# POWER.net
KiCad netlist of a schematic drawn in Altium Designer
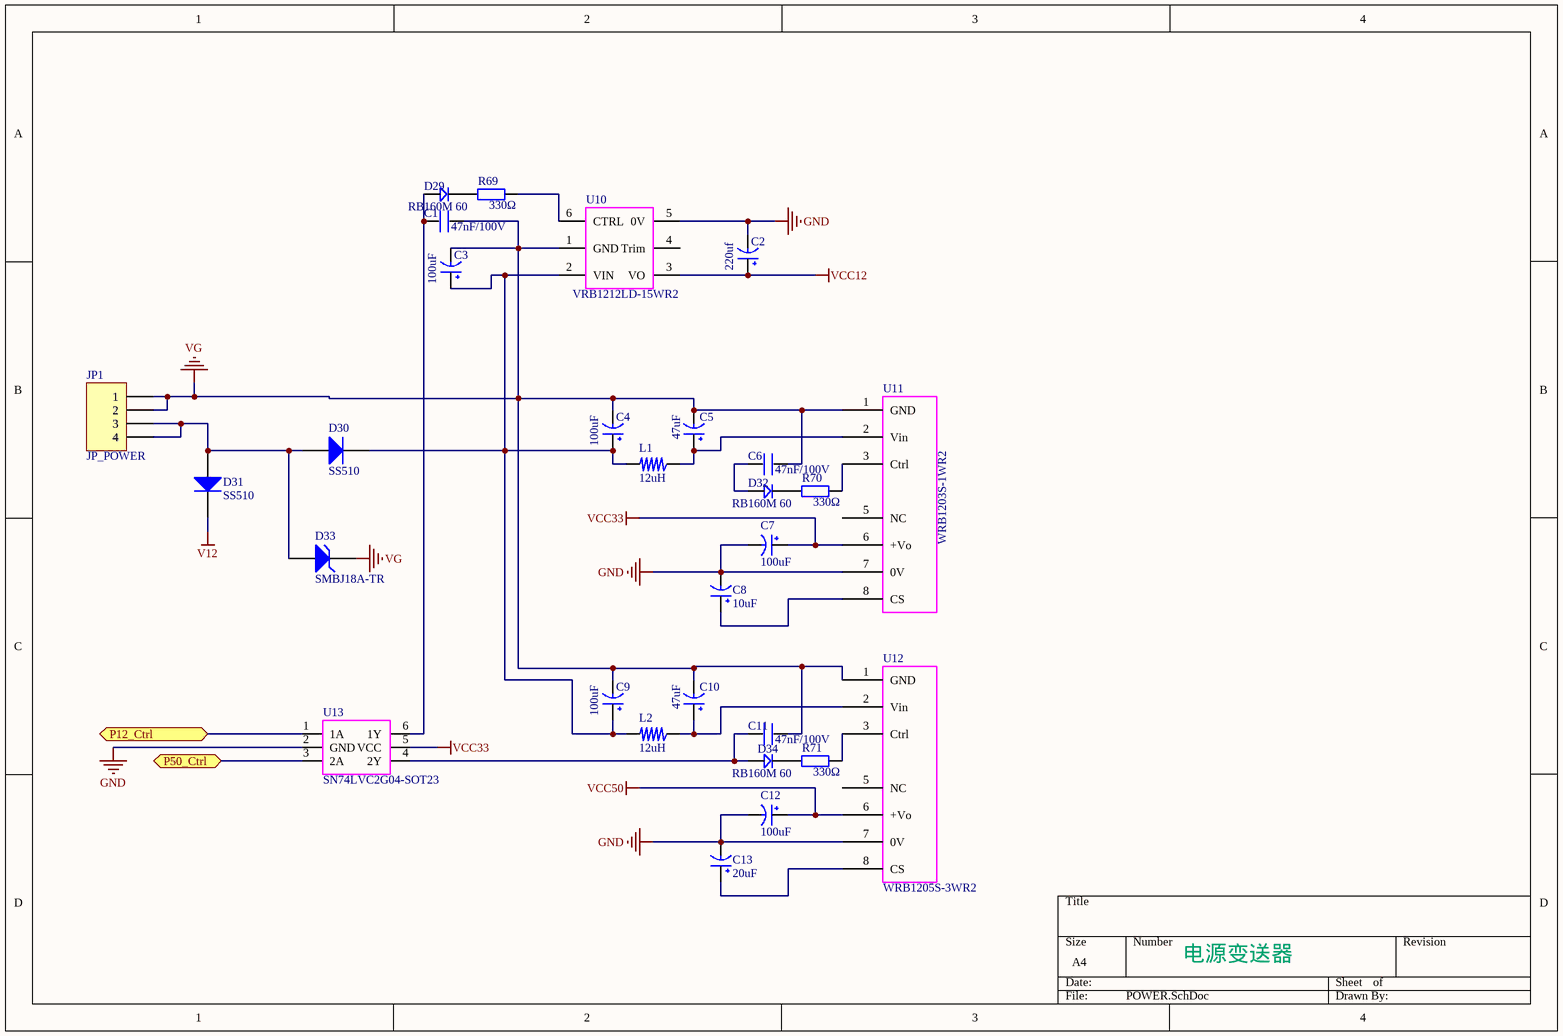
[diagram p0: POWER.SchDoc]

(export (version "E")
  (design (tool "Eeschema 10.0.6"))
  (components
    (comp (ref "C1") (value "47nF/100V") (footprint "0603P") (libsource (lib "WARSHIP") (part "C")))
    (comp (ref "C2") (value "220uf") (footprint "SMD-EC-F6.3") (libsource (lib "") (part "CAP_1")))
    (comp (ref "C3") (value "100uF") (footprint "SMD-EC-F6.3") (libsource (lib "") (part "CAP_1")))
    (comp (ref "C4") (value "100uF") (footprint "SMD-EC-F6.3") (libsource (lib "") (part "CAP_1")))
    (comp (ref "C5") (value "47uF") (footprint "SMD-EC-F6.3") (libsource (lib "") (part "CAP_1")))
    (comp (ref "C6") (value "47nF/100V") (footprint "0603P") (libsource (lib "WARSHIP") (part "C")))
    (comp (ref "C7") (value "100uF") (footprint "SMD-EC-F6.3") (libsource (lib "WARSHIP") (part "CAP")))
    (comp (ref "C8") (value "10uF") (footprint "SMD-EC-F4") (libsource (lib "") (part "CAP_1")))
    (comp (ref "C9") (value "100uF") (footprint "SMD-EC-F6.3") (libsource (lib "") (part "CAP_1")))
    (comp (ref "C10") (value "47uF") (footprint "SMD-EC-F6.3") (libsource (lib "") (part "CAP_1")))
    (comp (ref "C11") (value "47nF/100V") (footprint "0603P") (libsource (lib "WARSHIP") (part "C")))
    (comp (ref "C12") (value "100uF") (footprint "SMD-EC-F6.3") (libsource (lib "WARSHIP") (part "CAP")))
    (comp (ref "C13") (value "20uF") (footprint "SMD-EC-F4") (libsource (lib "") (part "CAP_1")))
    (comp (ref "D29") (value "RB160M 60") (footprint "SOD123/X.85") (libsource (lib "WARSHIP") (part "D")))
    (comp (ref "D30")
      (value "SS510")
      (footprint "SMC")
      (description "Default Diode")
      (fields (field (name "PUBLISHER") "Altium Limited"))
      (libsource (lib "Miscellaneous Devices") (part "Diode"))
    )
    (comp (ref "D31")
      (value "SS510")
      (footprint "SMC")
      (description "Default Diode")
      (fields (field (name "PUBLISHER") "Altium Limited"))
      (libsource (lib "Miscellaneous Devices") (part "Diode"))
    )
    (comp (ref "D32") (value "RB160M 60") (footprint "SOD123/X.85") (libsource (lib "WARSHIP") (part "D")))
    (comp (ref "D33")
      (value "SMBJ18A-TR")
      (footprint "DO-214")
      (description "Zener Diode")
      (fields (field (name "PUBLISHER") "Altium Limited"))
      (libsource (lib "Miscellaneous Devices") (part "D Zener"))
    )
    (comp (ref "D34") (value "RB160M 60") (footprint "SOD123/X.85") (libsource (lib "WARSHIP") (part "D")))
    (comp (ref "JP1")
      (value "JP_POWER")
      (footprint "3.81-4P")
      (description "Header, 4-Pin")
      (fields (field (name "PUBLISHER") "Altium Limited"))
      (libsource (lib "Miscellaneous Connectors") (part "Header 4"))
    )
    (comp (ref "L1") (value "12uH") (footprint "4R7_L_7_7_4") (libsource (lib "WARSHIP") (part "L_SOP")))
    (comp (ref "L2") (value "12uH") (footprint "4R7_L_7_7_4") (libsource (lib "WARSHIP") (part "L_SOP")))
    (comp (ref "R69")
      (value "330Ω")
      (footprint "1206")
      (description "Resistor")
      (fields (field (name "Comment") "Res2") (field (name "PUBLISHER") "Altium Limited"))
      (libsource (lib "Miscellaneous Devices") (part "Res2"))
    )
    (comp (ref "R70")
      (value "330Ω")
      (footprint "1206")
      (description "Resistor")
      (fields (field (name "Comment") "Res2") (field (name "PUBLISHER") "Altium Limited"))
      (libsource (lib "Miscellaneous Devices") (part "Res2"))
    )
    (comp (ref "R71")
      (value "330Ω")
      (footprint "1206")
      (description "Resistor")
      (fields (field (name "Comment") "Res2") (field (name "PUBLISHER") "Altium Limited"))
      (libsource (lib "Miscellaneous Devices") (part "Res2"))
    )
    (comp (ref "U10")
      (value "VRB1212LD-15WR2")
      (footprint "VRB1212LD-15WR2")
      (libsource (lib "VRB1212LD-15WR2") (part "VRB1212LD-15WR2"))
    )
    (comp (ref "U11")
      (value "WRB1203S-1WR2")
      (footprint "WRB120XS-XWR2")
      (libsource (lib "WRB1203S-1WR2") (part "WRB1203S-1WR2"))
    )
    (comp (ref "U12")
      (value "WRB1205S-3WR2")
      (footprint "WRB120XS-XWR2")
      (libsource (lib "WRB1203S-1WR2") (part "WRB1205S-3WR2"))
    )
    (comp (ref "U13")
      (value "SN74LVC2G04-SOT23")
      (footprint "SOT23-6")
      (libsource (lib "74hc245") (part "SN74LVC2G04-SOT23"))
    )
  )
  (nets
    (net (code "1") (name "/P12_Ctrl") (class "Default")
      (node (ref "U13") (pin "1") (pinfunction "1A_1") (pintype "passive"))
    )
    (net (code "2") (name "/P50_Ctrl") (class "Default")
      (node (ref "U13") (pin "3") (pinfunction "2A_3") (pintype "passive"))
    )
    (net (code "3") (name "GND") (class "Default")
      (node (ref "C12") (pin "2") (pinfunction "GND_2") (pintype "passive"))
      (node (ref "C13") (pin "2") (pinfunction "GND_2") (pintype "passive"))
      (node (ref "C2") (pin "2") (pinfunction "GND_2") (pintype "passive"))
      (node (ref "C7") (pin "2") (pinfunction "GND_2") (pintype "passive"))
      (node (ref "C8") (pin "2") (pinfunction "GND_2") (pintype "passive"))
      (node (ref "U10") (pin "5") (pinfunction "0V_5") (pintype "passive"))
      (node (ref "U11") (pin "7") (pinfunction "0V_7") (pintype "passive"))
      (node (ref "U12") (pin "7") (pinfunction "0V_7") (pintype "passive"))
      (node (ref "U13") (pin "2") (pinfunction "GND_2") (pintype "passive"))
    )
    (net (code "4") (name "Net-(C3-VCC)") (class "Default")
      (node (ref "C3") (pin "1") (pinfunction "VCC_1") (pintype "passive"))
      (node (ref "C4") (pin "1") (pinfunction "VCC_1") (pintype "passive"))
      (node (ref "C9") (pin "1") (pinfunction "VCC_1") (pintype "passive"))
      (node (ref "D30") (pin "2") (pinfunction "K_2") (pintype "passive"))
      (node (ref "L1") (pin "2") (pinfunction "2_2") (pintype "passive"))
      (node (ref "L2") (pin "2") (pinfunction "2_2") (pintype "passive"))
      (node (ref "U10") (pin "2") (pinfunction "VIN_2") (pintype "passive"))
    )
    (net (code "5") (name "Net-(C5-VCC)") (class "Default")
      (node (ref "C5") (pin "1") (pinfunction "VCC_1") (pintype "passive"))
      (node (ref "L1") (pin "1") (pinfunction "1_1") (pintype "passive"))
      (node (ref "U11") (pin "2") (pinfunction "Vin_2") (pintype "passive"))
    )
    (net (code "6") (name "Net-(C6-Pad1)") (class "Default")
      (node (ref "C6") (pin "1") (pintype "passive"))
      (node (ref "D32") (pin "1") (pintype "passive"))
    )
    (net (code "7") (name "Net-(C8-VCC)") (class "Default")
      (node (ref "C8") (pin "1") (pinfunction "VCC_1") (pintype "passive"))
      (node (ref "U11") (pin "8") (pinfunction "CS_8") (pintype "passive"))
    )
    (net (code "8") (name "Net-(C10-VCC)") (class "Default")
      (node (ref "C10") (pin "1") (pinfunction "VCC_1") (pintype "passive"))
      (node (ref "L2") (pin "1") (pinfunction "1_1") (pintype "passive"))
      (node (ref "U12") (pin "2") (pinfunction "Vin_2") (pintype "passive"))
    )
    (net (code "9") (name "Net-(C13-VCC)") (class "Default")
      (node (ref "C13") (pin "1") (pinfunction "VCC_1") (pintype "passive"))
      (node (ref "U12") (pin "8") (pinfunction "CS_8") (pintype "passive"))
    )
    (net (code "10") (name "Net-(D29-Pad2)") (class "Default")
      (node (ref "D29") (pin "2") (pintype "passive"))
      (node (ref "R69") (pin "2") (pinfunction "2_2") (pintype "passive"))
    )
    (net (code "11") (name "Net-(D30-A)") (class "Default")
      (node (ref "D30") (pin "1") (pinfunction "A_1") (pintype "passive"))
      (node (ref "D31") (pin "1") (pinfunction "A_1") (pintype "passive"))
      (node (ref "D33") (pin "1") (pinfunction "A_1") (pintype "passive"))
      (node (ref "JP1") (pin "3") (pinfunction "3_3") (pintype "passive"))
      (node (ref "JP1") (pin "4") (pinfunction "4_4") (pintype "passive"))
    )
    (net (code "12") (name "Net-(D32-Pad2)") (class "Default")
      (node (ref "D32") (pin "2") (pintype "passive"))
      (node (ref "R70") (pin "2") (pinfunction "2_2") (pintype "passive"))
    )
    (net (code "13") (name "Net-(D34-Pad2)") (class "Default")
      (node (ref "D34") (pin "2") (pintype "passive"))
      (node (ref "R71") (pin "2") (pinfunction "2_2") (pintype "passive"))
    )
    (net (code "14") (name "Net-(U10-CTRL)") (class "Default")
      (node (ref "R69") (pin "1") (pinfunction "1_1") (pintype "passive"))
      (node (ref "U10") (pin "6") (pinfunction "CTRL_6") (pintype "passive"))
    )
    (net (code "15") (name "Net-(U11-Ctrl)") (class "Default")
      (node (ref "R70") (pin "1") (pinfunction "1_1") (pintype "passive"))
      (node (ref "U11") (pin "3") (pinfunction "Ctrl_3") (pintype "passive"))
    )
    (net (code "16") (name "Net-(U12-Ctrl)") (class "Default")
      (node (ref "R71") (pin "1") (pinfunction "1_1") (pintype "passive"))
      (node (ref "U12") (pin "3") (pinfunction "Ctrl_3") (pintype "passive"))
    )
    (net (code "17") (name "Net-(U13-1Y)") (class "Default")
      (node (ref "C1") (pin "1") (pintype "passive"))
      (node (ref "D29") (pin "1") (pintype "passive"))
      (node (ref "U13") (pin "6") (pinfunction "1Y_6") (pintype "passive"))
    )
    (net (code "18") (name "Net-(U13-2Y)") (class "Default")
      (node (ref "C11") (pin "1") (pintype "passive"))
      (node (ref "D34") (pin "1") (pintype "passive"))
      (node (ref "U13") (pin "4") (pinfunction "2Y_4") (pintype "passive"))
    )
    (net (code "19") (name "V12") (class "Default")
      (node (ref "D31") (pin "2") (pinfunction "K_2") (pintype "passive"))
    )
    (net (code "20") (name "VCC12") (class "Default")
      (node (ref "C2") (pin "1") (pinfunction "VCC_1") (pintype "passive"))
      (node (ref "U10") (pin "3") (pinfunction "VO_3") (pintype "passive"))
    )
    (net (code "21") (name "VCC33") (class "Default")
      (node (ref "C7") (pin "1") (pinfunction "VCC_1") (pintype "passive"))
      (node (ref "U11") (pin "6") (pinfunction "+Vo_6") (pintype "passive"))
      (node (ref "U13") (pin "5") (pinfunction "VCC_5") (pintype "passive"))
    )
    (net (code "22") (name "VCC50") (class "Default")
      (node (ref "C12") (pin "1") (pinfunction "VCC_1") (pintype "passive"))
      (node (ref "U12") (pin "6") (pinfunction "+Vo_6") (pintype "passive"))
    )
    (net (code "23") (name "VG") (class "Default")
      (node (ref "C1") (pin "2") (pintype "passive"))
      (node (ref "C10") (pin "2") (pinfunction "GND_2") (pintype "passive"))
      (node (ref "C11") (pin "2") (pintype "passive"))
      (node (ref "C3") (pin "2") (pinfunction "GND_2") (pintype "passive"))
      (node (ref "C4") (pin "2") (pinfunction "GND_2") (pintype "passive"))
      (node (ref "C5") (pin "2") (pinfunction "GND_2") (pintype "passive"))
      (node (ref "C6") (pin "2") (pintype "passive"))
      (node (ref "C9") (pin "2") (pinfunction "GND_2") (pintype "passive"))
      (node (ref "D33") (pin "2") (pinfunction "K_2") (pintype "passive"))
      (node (ref "JP1") (pin "1") (pinfunction "1_1") (pintype "passive"))
      (node (ref "JP1") (pin "2") (pinfunction "2_2") (pintype "passive"))
      (node (ref "U10") (pin "1") (pinfunction "GND_1") (pintype "passive"))
      (node (ref "U11") (pin "1") (pinfunction "GND_1") (pintype "passive"))
      (node (ref "U12") (pin "1") (pinfunction "GND_1") (pintype "passive"))
    )
    (net (code "24") (name "unconnected-(U10-Trim-Pad4)") (class "Default")
      (node (ref "U10") (pin "4") (pinfunction "Trim_4") (pintype "passive"))
    )
    (net (code "25") (name "unconnected-(U11-NC-Pad5)") (class "Default")
      (node (ref "U11") (pin "5") (pinfunction "NC_5") (pintype "passive"))
    )
    (net (code "26") (name "unconnected-(U12-NC-Pad5)") (class "Default")
      (node (ref "U12") (pin "5") (pinfunction "NC_5") (pintype "passive"))
    )
  )
)
